# MS5611.net
KiCad netlist of a schematic drawn in Altium Designer
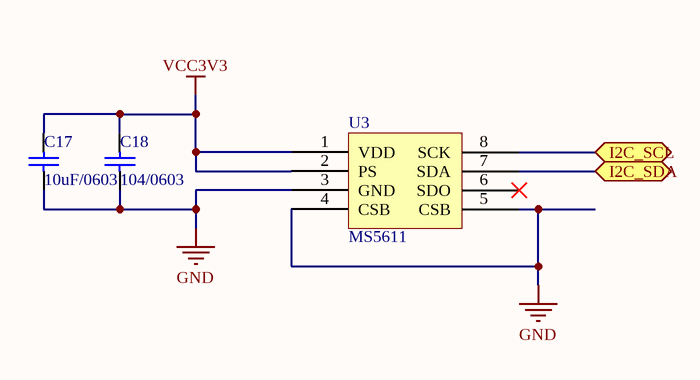
[diagram p0: MS5611.SchDoc]

(export (version "E")
  (design (tool "Eeschema 10.0.6"))
  (components
    (comp (ref "C17")
      (value "10uF/0603")
      (footprint "C0603")
      (description "无极性贴片电容")
      (libsource (lib "常用原件") (part "CAP"))
    )
    (comp (ref "C18")
      (value "104/0603")
      (footprint "C0603")
      (description "无极性贴片电容")
      (libsource (lib "常用原件") (part "CAP"))
    )
    (comp (ref "U3")
      (value "MS5611")
      (footprint "MS5611")
      (description "barometer")
      (libsource (lib "Schlib1") (part "MS5611"))
    )
  )
  (nets
    (net (code "1") (name "/I2C_SCL") (class "Default")
      (node (ref "U3") (pin "8") (pinfunction "SCK_8") (pintype "passive"))
    )
    (net (code "2") (name "/I2C_SDA") (class "Default")
      (node (ref "U3") (pin "7") (pinfunction "SDA_7") (pintype "passive"))
    )
    (net (code "3") (name "GND") (class "Default")
      (node (ref "C17") (pin "1") (pinfunction "1_1") (pintype "passive"))
      (node (ref "C18") (pin "1") (pinfunction "1_1") (pintype "passive"))
      (node (ref "U3") (pin "3") (pinfunction "GND_3") (pintype "passive"))
      (node (ref "U3") (pin "4") (pinfunction "CSB_4") (pintype "passive"))
      (node (ref "U3") (pin "5") (pinfunction "CSB_5") (pintype "passive"))
    )
    (net (code "4") (name "VCC3V3") (class "Default")
      (node (ref "C17") (pin "2") (pinfunction "2_2") (pintype "passive"))
      (node (ref "C18") (pin "2") (pinfunction "2_2") (pintype "passive"))
      (node (ref "U3") (pin "1") (pinfunction "VDD_1") (pintype "passive"))
      (node (ref "U3") (pin "2") (pinfunction "PS_2") (pintype "passive"))
    )
    (net (code "5") (name "unconnected-(U3-SDO-Pad6)") (class "Default")
      (node (ref "U3") (pin "6") (pinfunction "SDO_6") (pintype "passive+no_connect"))
    )
  )
)
